# ATLAS.net
KiCad netlist of a schematic drawn in EasyEDA Pro
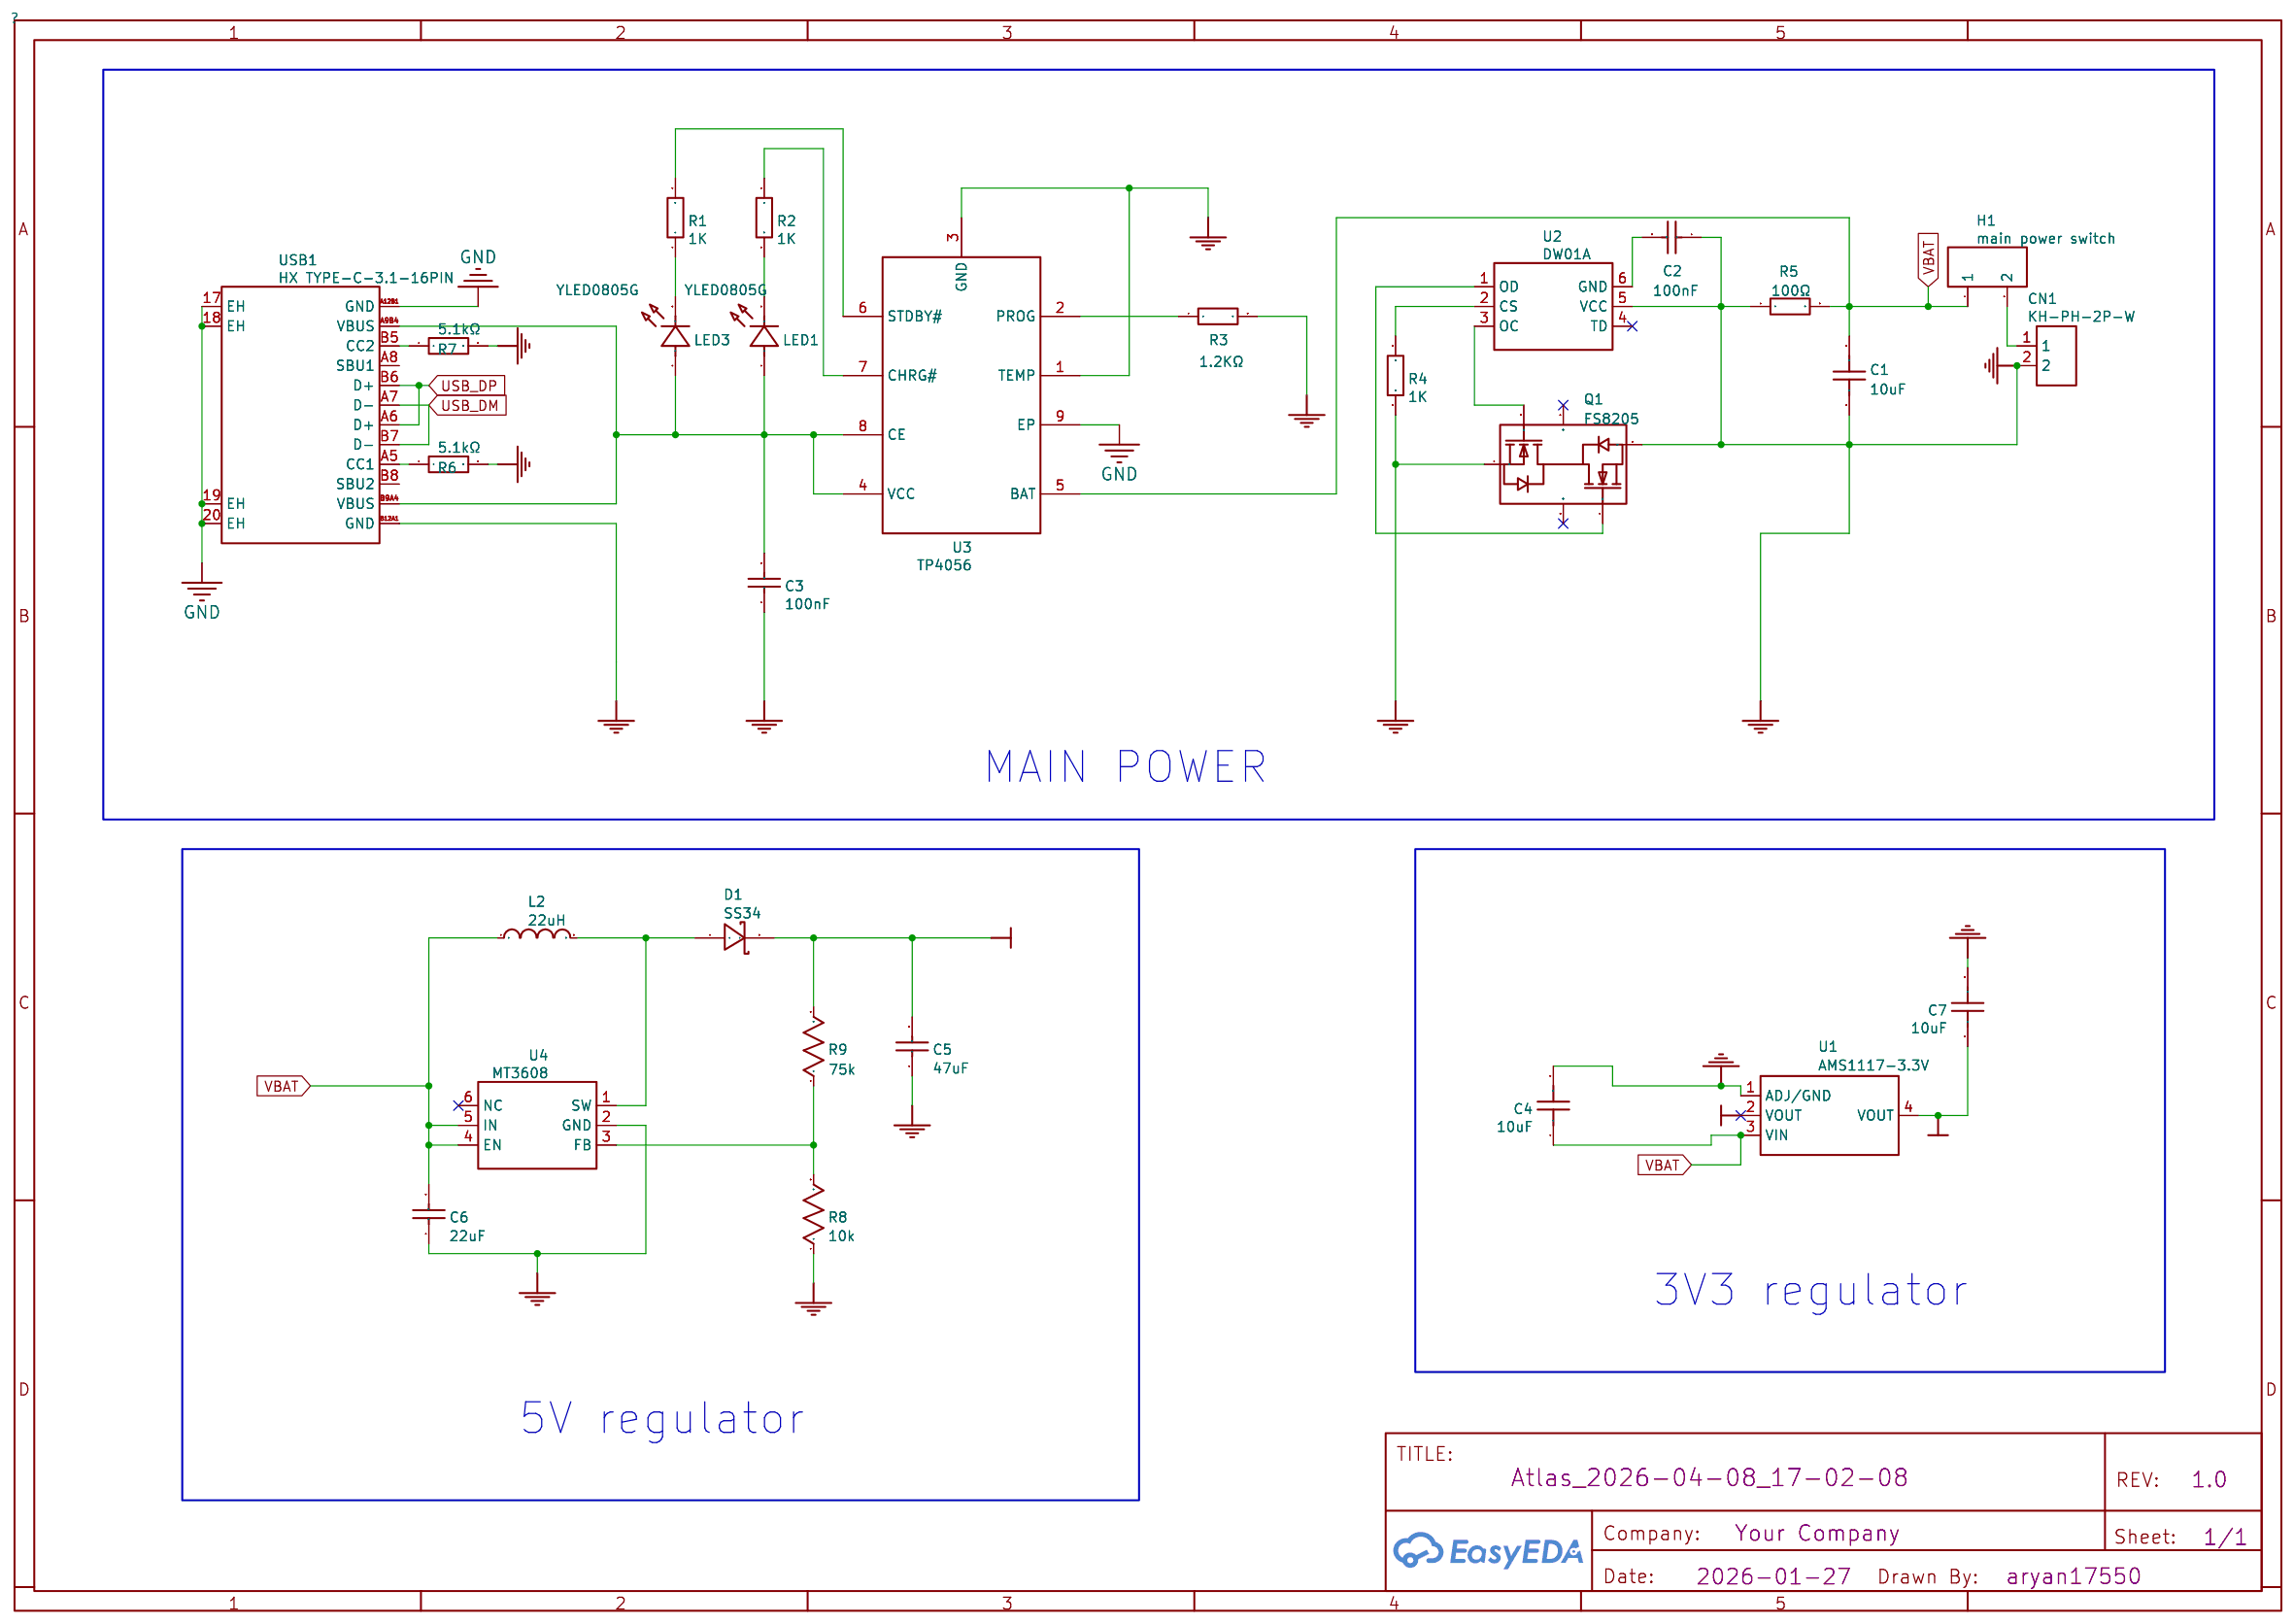
[diagram p0: Sheet_1]
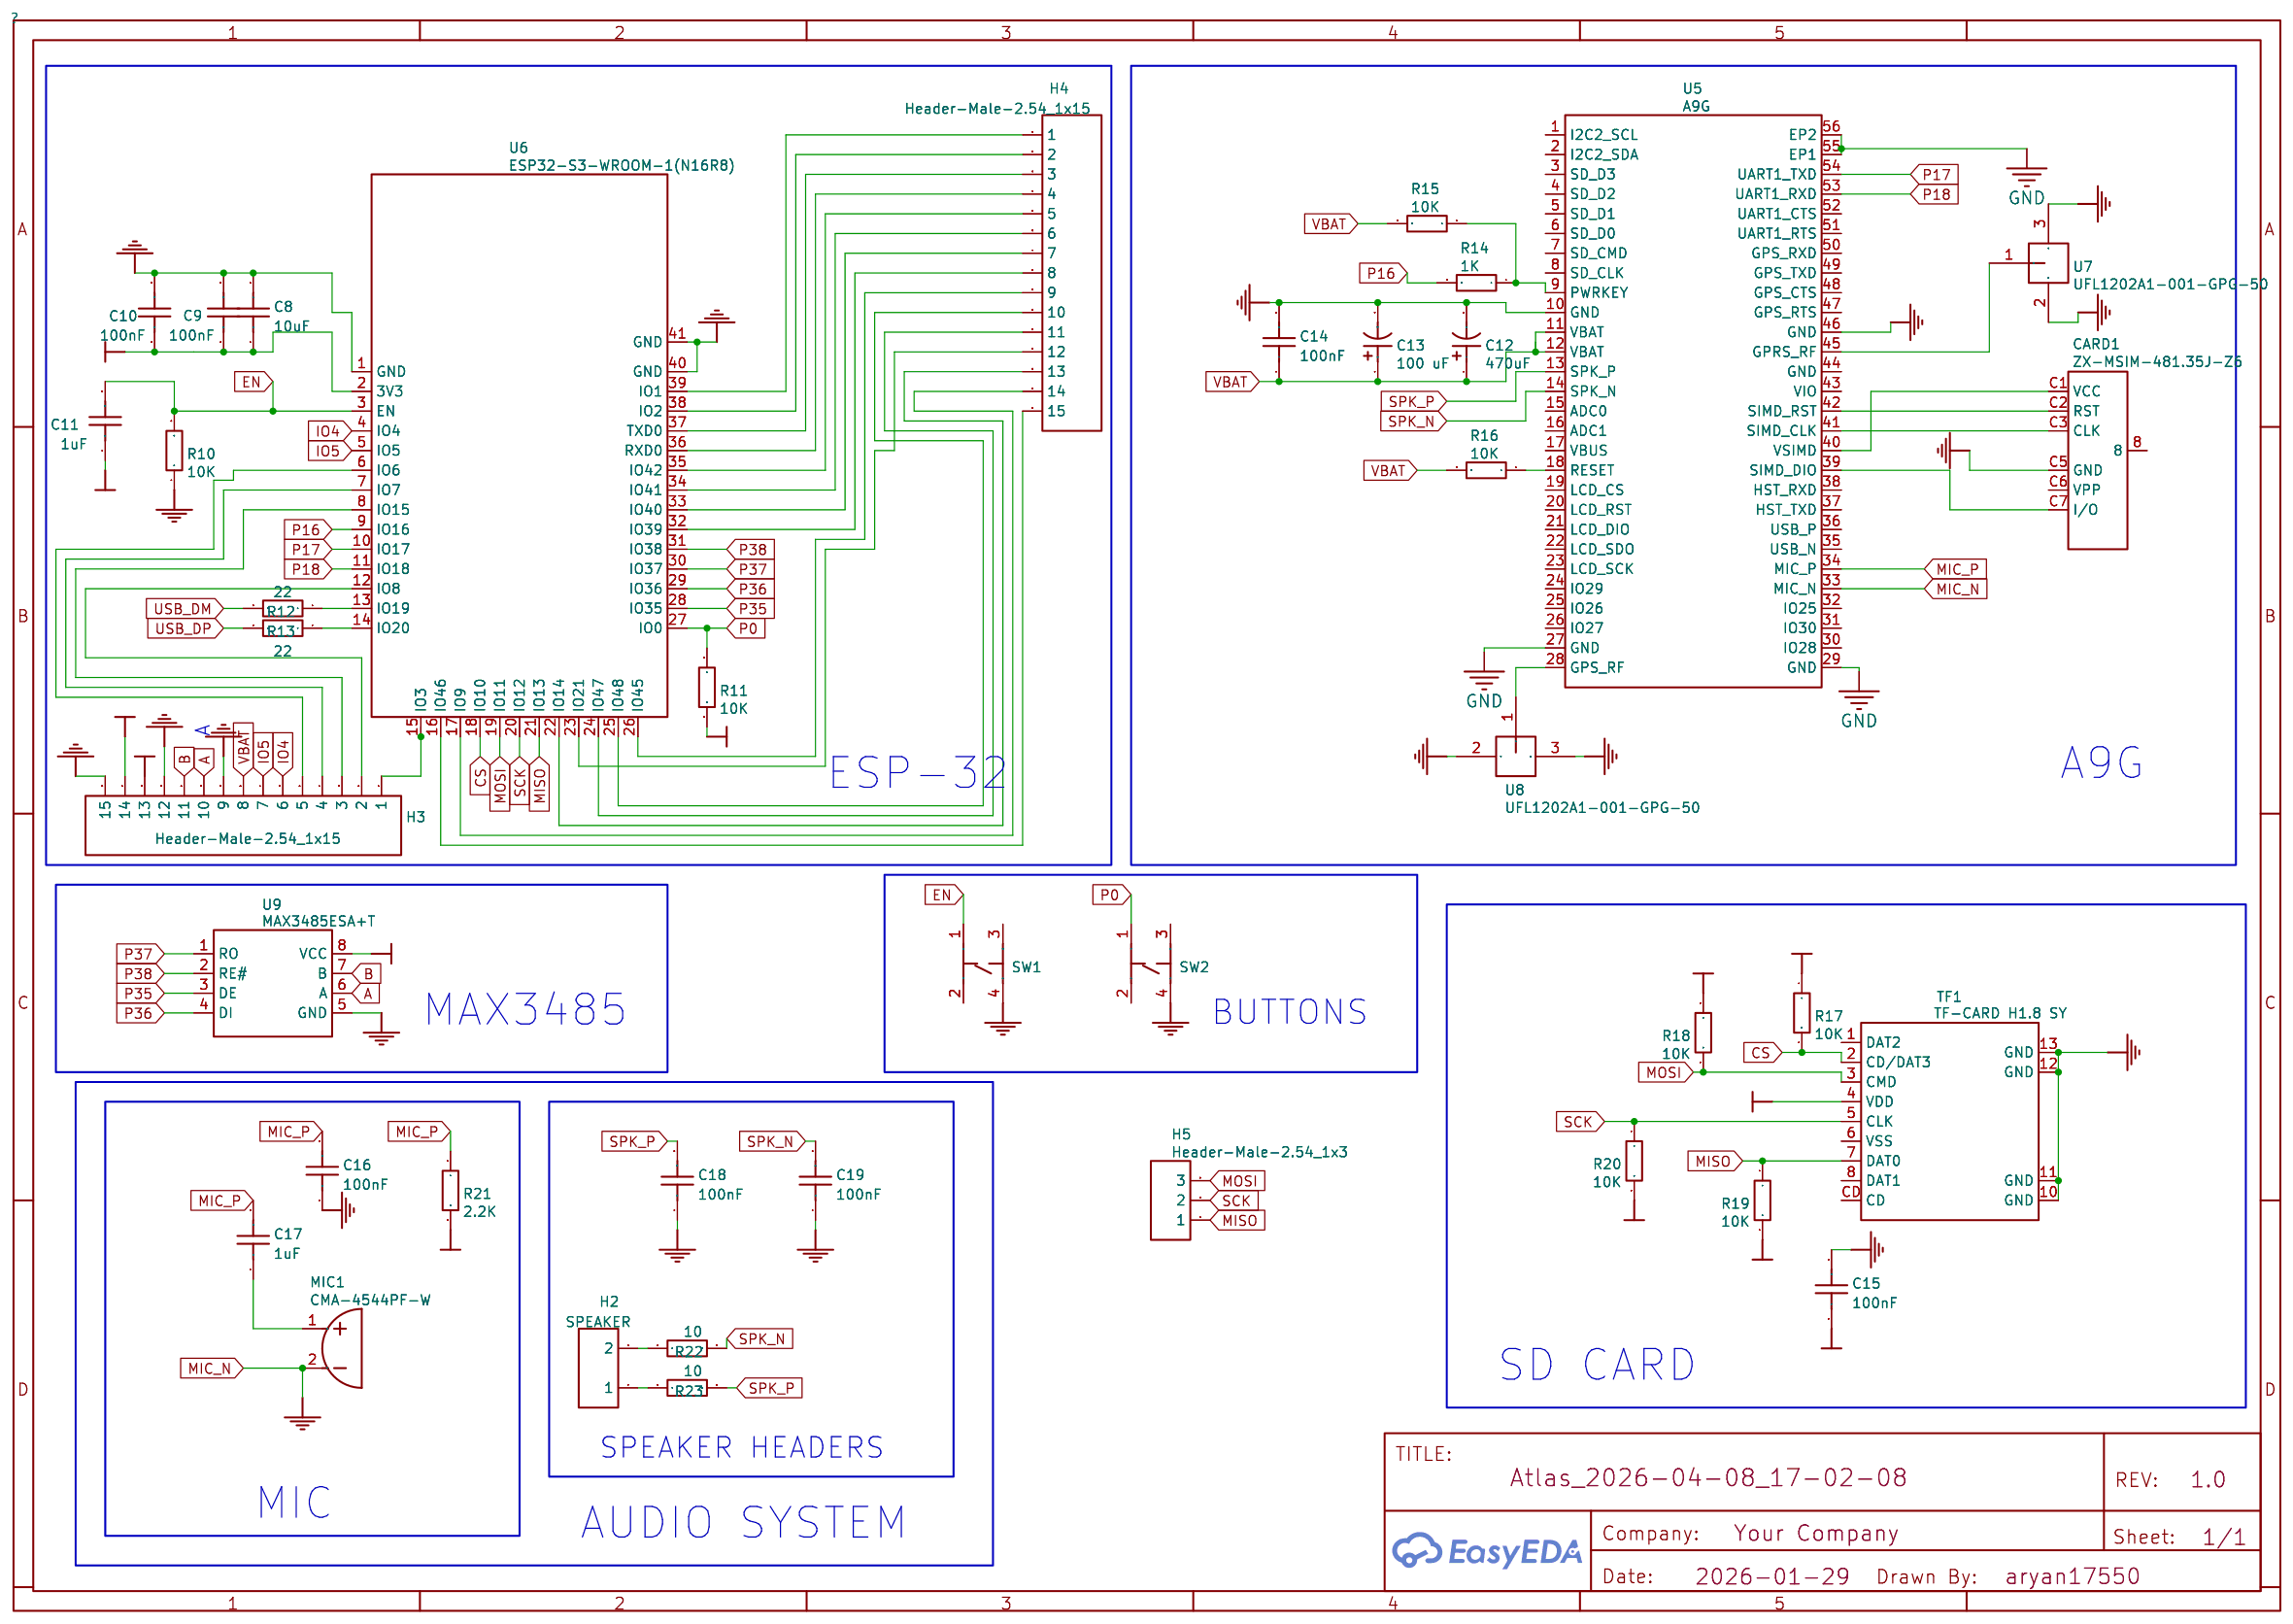
[diagram p1: Sheet_2]

(export (version "E")
  (design (tool "Eeschema 10.0.6"))
  (components
    (comp (ref "C1")
      (value "10uF")
      (footprint "easyedapro:C0603")
      (fields (field (name "Manufacturer Part") "CL10A106MP8NNNC") (field (name "Manufacturer") "SAMSUNG"))
      (libsource (lib "") (part "10uF_1"))
    )
    (comp (ref "C2")
      (value "100nF")
      (footprint "easyedapro:C0603")
      (fields (field (name "Manufacturer Part") "0603B104K250") (field (name "Manufacturer") "WTC"))
      (libsource (lib "easyedapro") (part "100nF"))
    )
    (comp (ref "C3")
      (value "100nF")
      (footprint "easyedapro:C0603")
      (fields (field (name "Manufacturer Part") "0603B104K250") (field (name "Manufacturer") "WTC"))
      (libsource (lib "easyedapro") (part "100nF"))
    )
    (comp (ref "C4")
      (value "10uF")
      (footprint "easyedapro:C0603")
      (fields (field (name "Manufacturer Part") "CL10A106MP8NNNC") (field (name "Manufacturer") "SAMSUNG"))
      (libsource (lib "easyedapro") (part "10uF"))
    )
    (comp (ref "C5")
      (value "47uF")
      (footprint "easyedapro:C0603")
      (fields (field (name "Manufacturer Part") "1812X226K250NT") (field (name "Manufacturer") "FH"))
      (libsource (lib "easyedapro") (part "47uF"))
    )
    (comp (ref "C6")
      (value "22uF")
      (footprint "easyedapro:C0603")
      (fields (field (name "Manufacturer Part") "1812X226K250NT") (field (name "Manufacturer") "FH"))
      (libsource (lib "easyedapro") (part "22uF"))
    )
    (comp (ref "C7")
      (value "10uF")
      (footprint "easyedapro:C0603")
      (fields (field (name "Manufacturer Part") "CL10A106MP8NNNC") (field (name "Manufacturer") "SAMSUNG"))
      (libsource (lib "easyedapro") (part "10uF"))
    )
    (comp (ref "CN1")
      (value "KH-PH-2P-W")
      (footprint "easyedapro:CONN-TH_2P-P2.00_KINGHELM_KH-PH-2P-W")
      (fields (field (name "Manufacturer") "kinghelm(金航标)") (field (name "Contributor") "LCSC"))
      (libsource (lib "easyedapro") (part "KH-PH-2P-W"))
    )
    (comp (ref "D1")
      (value "SS34")
      (footprint "easyedapro:SS34")
      (fields (field (name "Manufacturer") "MDD"))
      (libsource (lib "easyedapro") (part "SS34"))
    )
    (comp (ref "H1")
      (value "main power switch")
      (footprint "easyedapro:HDR-TH_2P-P2.54-V-M-1")
      (fields
        (field (name "Manufacturer Part") "826629-2")
        (field (name "Manufacturer") "TE Connectivity(泰科电子)")
      )
      (libsource (lib "easyedapro") (part "main power switch"))
    )
    (comp (ref "L2")
      (value "22uH")
      (footprint "easyedapro:IND-SMD_L12.5-W12.5_CYH125-22UH")
      (fields (field (name "Manufacturer Part") "SMRH74-220MT") (field (name "Manufacturer") "SXN(顺翔诺)"))
      (libsource (lib "easyedapro") (part "22uH"))
    )
    (comp (ref "LED1")
      (value "YLED0805G")
      (footprint "easyedapro:LED0805-FD-GREEN")
      (fields (field (name "Manufacturer") "YONGYUTAI(永裕泰)") (field (name "Contributor") "lcsc"))
      (libsource (lib "easyedapro") (part "YLED0805G"))
    )
    (comp (ref "LED3")
      (value "YLED0805G")
      (footprint "easyedapro:LED0805-FD-GREEN")
      (fields (field (name "Manufacturer") "YONGYUTAI(永裕泰)") (field (name "Contributor") "lcsc"))
      (libsource (lib "easyedapro") (part "YLED0805G"))
    )
    (comp (ref "Q1")
      (value "FS8205")
      (footprint "easyedapro:FS8205A")
      (fields (field (name "Manufacturer") "FORTUNE"))
      (libsource (lib "easyedapro") (part "FS8205"))
    )
    (comp (ref "R1")
      (value "1K")
      (footprint "easyedapro:R0603")
      (fields
        (field (name "Manufacturer Part") "ERJ3GEYJ102V")
        (field (name "Manufacturer") "PANASONIC")
        (field (name "Contributor") "LCSC")
      )
      (libsource (lib "easyedapro") (part "1K"))
    )
    (comp (ref "R2")
      (value "1K")
      (footprint "easyedapro:R0603")
      (fields
        (field (name "Manufacturer Part") "ERJ3GEYJ102V")
        (field (name "Manufacturer") "PANASONIC")
        (field (name "Contributor") "LCSC")
      )
      (libsource (lib "") (part "1K_1"))
    )
    (comp (ref "R3")
      (value "1.2KΩ")
      (footprint "easyedapro:R0603")
      (fields (field (name "Manufacturer Part") "RC0603JR-071K2L") (field (name "Manufacturer") "YAGEO"))
      (libsource (lib "easyedapro") (part "1.2KΩ"))
    )
    (comp (ref "R4")
      (value "1K")
      (footprint "easyedapro:R0603")
      (fields
        (field (name "Manufacturer Part") "ERJ3GEYJ102V")
        (field (name "Manufacturer") "PANASONIC")
        (field (name "Contributor") "LCSC")
      )
      (libsource (lib "easyedapro") (part "1K"))
    )
    (comp (ref "R5")
      (value "100Ω")
      (footprint "easyedapro:R0603")
      (fields (field (name "Manufacturer Part") "0603WAJ0101T5E") (field (name "Manufacturer") "UniOhm"))
      (libsource (lib "easyedapro") (part "100Ω"))
    )
    (comp (ref "R6")
      (value "5.1kΩ")
      (footprint "easyedapro:R0603")
      (fields
        (field (name "Manufacturer Part") "RMC06035.1K1%N")
        (field (name "Manufacturer") "Tyohm(幸亚电阻)")
        (field (name "Contributor") "LCSC")
      )
      (libsource (lib "easyedapro") (part "5.1kΩ"))
    )
    (comp (ref "R7")
      (value "5.1kΩ")
      (footprint "easyedapro:R0603")
      (fields
        (field (name "Manufacturer Part") "RMC06035.1K1%N")
        (field (name "Manufacturer") "Tyohm(幸亚电阻)")
        (field (name "Contributor") "LCSC")
      )
      (libsource (lib "easyedapro") (part "5.1kΩ"))
    )
    (comp (ref "R8")
      (value "10k")
      (footprint "easyedapro:R0603")
      (fields (field (name "Manufacturer Part") "?") (field (name "Manufacturer") "PANASONIC"))
      (libsource (lib "easyedapro") (part "10k"))
    )
    (comp (ref "R9")
      (value "75k")
      (footprint "easyedapro:R0603")
      (fields (field (name "Manufacturer Part") "?"))
      (libsource (lib "easyedapro") (part "75k"))
    )
    (comp (ref "U1")
      (value "AMS1117-3.3V")
      (footprint "easyedapro:SOT-223-4_L6.5-W3.5-P2.30-LS7.0-BR")
      (fields (field (name "Manufacturer") "WPMtek(维攀)") (field (name "Contributor") "LCSC"))
      (libsource (lib "easyedapro") (part "AMS1117-3.3V"))
    )
    (comp (ref "U2")
      (value "DW01A")
      (footprint "easyedapro:DW01A")
      (fields (field (name "Manufacturer") "PUOLOP") (field (name "Contributor") "LCSC"))
      (libsource (lib "easyedapro") (part "DW01A"))
    )
    (comp (ref "U3")
      (value "TP4056")
      (footprint "easyedapro:ESOP-8_L4.9-W3.9-P1.27-LS6.0-BL-EP")
      (fields
        (field (name "Manufacturer Part") "TP4056-42-ESOP8")
        (field (name "Manufacturer") "TOPPOWER(南京拓微)")
        (field (name "Contributor") "Guest")
      )
      (libsource (lib "easyedapro") (part "TP4056"))
    )
    (comp (ref "U4")
      (value "MT3608")
      (footprint "easyedapro:MT3608")
      (fields (field (name "Manufacturer") "AEROSEMI"))
      (libsource (lib "easyedapro") (part "MT3608"))
    )
    (comp (ref "USB1")
      (value "HX TYPE-C-3.1-16PIN")
      (footprint "easyedapro:TYPE-C-SMD_HX-TYPE-C-16PIN")
      (fields (field (name "Manufacturer") "hanxia(韩下)") (field (name "Contributor") "lcsc"))
      (libsource (lib "easyedapro") (part "HX TYPE-C-3.1-16PIN"))
    )
    (comp (ref "C8")
      (value "10uF")
      (footprint "easyedapro:C0603")
      (fields (field (name "Manufacturer Part") "CL10A106MP8NNNC") (field (name "Manufacturer") "SAMSUNG"))
      (libsource (lib "easyedapro") (part "10uF"))
    )
    (comp (ref "C9")
      (value "100nF")
      (footprint "easyedapro:C0603")
      (fields (field (name "Manufacturer Part") "CL10A106MP8NNNC") (field (name "Manufacturer") "SAMSUNG"))
      (libsource (lib "easyedapro") (part "100nF"))
    )
    (comp (ref "C10")
      (value "100nF")
      (footprint "easyedapro:C0603")
      (fields (field (name "Manufacturer Part") "CL10A106MP8NNNC") (field (name "Manufacturer") "SAMSUNG"))
      (libsource (lib "easyedapro") (part "100nF"))
    )
    (comp (ref "C11")
      (value "1uF")
      (footprint "easyedapro:C0603")
      (fields (field (name "Manufacturer Part") "CL10A106MP8NNNC") (field (name "Manufacturer") "SAMSUNG"))
      (libsource (lib "easyedapro") (part "1uF"))
    )
    (comp (ref "C12")
      (value "470uF")
      (footprint "easyedapro:CAP-SMD_BD10.0-L10.3-W10.3-LS11.3-FD")
      (fields
        (field (name "Manufacturer Part") "CS470UF35V167RV0136")
        (field (name "Manufacturer") "KNSCHA(科尼盛)")
        (field (name "Contributor") "lcsc")
      )
      (libsource (lib "easyedapro") (part "470uF"))
    )
    (comp (ref "C13")
      (value "100 uF")
      (footprint "easyedapro:CAP-SMD_BD10.0-L10.3-W10.3-LS11.3-FD")
      (fields
        (field (name "Manufacturer Part") "CS470UF35V167RV0136")
        (field (name "Manufacturer") "KNSCHA(科尼盛)")
        (field (name "Contributor") "lcsc")
      )
      (libsource (lib "easyedapro") (part "100 uF"))
    )
    (comp (ref "C14")
      (value "100nF")
      (footprint "easyedapro:C0603")
      (fields (field (name "Manufacturer Part") "CL10A106MP8NNNC") (field (name "Manufacturer") "SAMSUNG"))
      (libsource (lib "easyedapro") (part "100nF"))
    )
    (comp (ref "C15")
      (value "100nF")
      (footprint "easyedapro:C0603")
      (fields (field (name "Manufacturer Part") "CL10A106MP8NNNC") (field (name "Manufacturer") "SAMSUNG"))
      (libsource (lib "easyedapro") (part "100nF"))
    )
    (comp (ref "C16")
      (value "100nF")
      (footprint "easyedapro:C0603")
      (fields (field (name "Manufacturer Part") "CL10A106MP8NNNC") (field (name "Manufacturer") "SAMSUNG"))
      (libsource (lib "easyedapro") (part "100nF"))
    )
    (comp (ref "C17")
      (value "1uF")
      (footprint "easyedapro:C0603")
      (fields (field (name "Manufacturer Part") "CL10A106MP8NNNC") (field (name "Manufacturer") "SAMSUNG"))
      (libsource (lib "easyedapro") (part "1uF"))
    )
    (comp (ref "C18")
      (value "100nF")
      (footprint "easyedapro:C0603")
      (fields (field (name "Manufacturer Part") "CL10A106MP8NNNC") (field (name "Manufacturer") "SAMSUNG"))
      (libsource (lib "easyedapro") (part "100nF"))
    )
    (comp (ref "C19")
      (value "100nF")
      (footprint "easyedapro:C0603")
      (fields (field (name "Manufacturer Part") "CL10A106MP8NNNC") (field (name "Manufacturer") "SAMSUNG"))
      (libsource (lib "easyedapro") (part "100nF"))
    )
    (comp (ref "CARD1")
      (value "ZX-MSIM-481.35J-Z6")
      (footprint "easyedapro:SIM-SMD_ZX-MSIM-481.35J-Z6")
      (fields (field (name "Manufacturer") "Megastar(兆星)") (field (name "Contributor") "lcsc"))
      (libsource (lib "easyedapro") (part "ZX-MSIM-481.35J-Z6"))
    )
    (comp (ref "H2")
      (value "SPEAKER")
      (footprint "easyedapro:HDR-TH_2P-P2.54-V-M-1")
      (fields
        (field (name "Manufacturer Part") "826629-2")
        (field (name "Manufacturer") "TE Connectivity(泰科电子)")
      )
      (libsource (lib "easyedapro") (part "SPEAKER"))
    )
    (comp (ref "H3")
      (value "Header-Male-2.54_1x15")
      (footprint "easyedapro:HDR-TH_15P-P2.54-V-M")
      (fields
        (field (name "Manufacturer Part") "B-2100S15P-A110")
        (field (name "Manufacturer") "Ckmtw(灿科盟)")
        (field (name "Contributor") "LCSC")
      )
      (libsource (lib "easyedapro") (part "Header-Male-2.54_1x15"))
    )
    (comp (ref "H4")
      (value "Header-Male-2.54_1x15")
      (footprint "easyedapro:HDR-TH_15P-P2.54-V-M")
      (fields
        (field (name "Manufacturer Part") "B-2100S15P-A110")
        (field (name "Manufacturer") "Ckmtw(灿科盟)")
        (field (name "Contributor") "LCSC")
      )
      (libsource (lib "") (part "Header-Male-2.54_1x15_1"))
    )
    (comp (ref "H5")
      (value "Header-Male-2.54_1x3")
      (footprint "easyedapro:HDR-TH_3P-P2.54-V-M-1")
      (fields (field (name "Manufacturer Part") "2.54-1*3P针") (field (name "Manufacturer") "BOOMELE(博穆精密)"))
      (libsource (lib "easyedapro") (part "Header-Male-2.54_1x3"))
    )
    (comp (ref "MIC1")
      (value "CMA-4544PF-W")
      (footprint "easyedapro:MIC-TH_BD9.7-P2.50-D0.8-L-FD")
      (fields (field (name "Manufacturer") "CUI") (field (name "Contributor") "lcsc"))
      (libsource (lib "easyedapro") (part "CMA-4544PF-W"))
    )
    (comp (ref "R10")
      (value "10K")
      (footprint "easyedapro:R0603")
      (fields
        (field (name "Manufacturer Part") "ERJ3GEYJ102V")
        (field (name "Manufacturer") "PANASONIC")
        (field (name "Contributor") "LCSC")
      )
      (libsource (lib "") (part "10K_1"))
    )
    (comp (ref "R11")
      (value "10K")
      (footprint "easyedapro:R0603")
      (fields
        (field (name "Manufacturer Part") "ERJ3GEYJ102V")
        (field (name "Manufacturer") "PANASONIC")
        (field (name "Contributor") "LCSC")
      )
      (libsource (lib "") (part "10K_1"))
    )
    (comp (ref "R12")
      (value "22")
      (footprint "easyedapro:R0603")
      (fields
        (field (name "Manufacturer Part") "ERJ3GEYJ102V")
        (field (name "Manufacturer") "PANASONIC")
        (field (name "Contributor") "LCSC")
      )
      (libsource (lib "easyedapro") (part "22"))
    )
    (comp (ref "R13")
      (value "22")
      (footprint "easyedapro:R0603")
      (fields
        (field (name "Manufacturer Part") "ERJ3GEYJ102V")
        (field (name "Manufacturer") "PANASONIC")
        (field (name "Contributor") "LCSC")
      )
      (libsource (lib "easyedapro") (part "22"))
    )
    (comp (ref "R14")
      (value "1K")
      (footprint "easyedapro:R0603")
      (fields
        (field (name "Manufacturer Part") "ERJ3GEYJ102V")
        (field (name "Manufacturer") "PANASONIC")
        (field (name "Contributor") "LCSC")
      )
      (libsource (lib "easyedapro") (part "1K"))
    )
    (comp (ref "R15")
      (value "10K")
      (footprint "easyedapro:R0603")
      (fields
        (field (name "Manufacturer Part") "ERJ3GEYJ102V")
        (field (name "Manufacturer") "PANASONIC")
        (field (name "Contributor") "LCSC")
      )
      (libsource (lib "") (part "10K_2"))
    )
    (comp (ref "R16")
      (value "10K")
      (footprint "easyedapro:R0603")
      (fields
        (field (name "Manufacturer Part") "ERJ3GEYJ102V")
        (field (name "Manufacturer") "PANASONIC")
        (field (name "Contributor") "LCSC")
      )
      (libsource (lib "") (part "10K_2"))
    )
    (comp (ref "R17")
      (value "10K")
      (footprint "easyedapro:R0603")
      (fields
        (field (name "Manufacturer Part") "ERJ3GEYJ102V")
        (field (name "Manufacturer") "PANASONIC")
        (field (name "Contributor") "LCSC")
      )
      (libsource (lib "easyedapro") (part "10K"))
    )
    (comp (ref "R18")
      (value "10K")
      (footprint "easyedapro:R0603")
      (fields
        (field (name "Manufacturer Part") "ERJ3GEYJ102V")
        (field (name "Manufacturer") "PANASONIC")
        (field (name "Contributor") "LCSC")
      )
      (libsource (lib "easyedapro") (part "10K"))
    )
    (comp (ref "R19")
      (value "10K")
      (footprint "easyedapro:R0603")
      (fields
        (field (name "Manufacturer Part") "ERJ3GEYJ102V")
        (field (name "Manufacturer") "PANASONIC")
        (field (name "Contributor") "LCSC")
      )
      (libsource (lib "easyedapro") (part "10K"))
    )
    (comp (ref "R20")
      (value "10K")
      (footprint "easyedapro:R0603")
      (fields
        (field (name "Manufacturer Part") "ERJ3GEYJ102V")
        (field (name "Manufacturer") "PANASONIC")
        (field (name "Contributor") "LCSC")
      )
      (libsource (lib "easyedapro") (part "10K"))
    )
    (comp (ref "R21")
      (value "2.2K")
      (footprint "easyedapro:R0603")
      (fields
        (field (name "Manufacturer Part") "ERJ3GEYJ102V")
        (field (name "Manufacturer") "PANASONIC")
        (field (name "Contributor") "LCSC")
      )
      (libsource (lib "easyedapro") (part "2.2K"))
    )
    (comp (ref "R22")
      (value "10")
      (footprint "easyedapro:R0603")
      (fields
        (field (name "Manufacturer Part") "ERJ3GEYJ102V")
        (field (name "Manufacturer") "PANASONIC")
        (field (name "Contributor") "LCSC")
      )
      (libsource (lib "easyedapro") (part "10"))
    )
    (comp (ref "R23")
      (value "10")
      (footprint "easyedapro:R0603")
      (fields
        (field (name "Manufacturer Part") "ERJ3GEYJ102V")
        (field (name "Manufacturer") "PANASONIC")
        (field (name "Contributor") "LCSC")
      )
      (libsource (lib "easyedapro") (part "10"))
    )
    (comp (ref "SW1")
      (value "HX-6X6X7.3-TP FT SQUARE BUTTON")
      (footprint "easyedapro:SW-SMD_4P-L6.0-W6.0-P4.50-LS9.0-H7.3")
      (fields
        (field (name "Manufacturer Part") "HX-6x6x7.3-TP FT square button")
        (field (name "Manufacturer") "hanxia(韩下)")
        (field (name "Contributor") "lcsc")
      )
      (libsource (lib "easyedapro") (part "HX-6X6X7.3-TP FT SQUARE BUTTON"))
    )
    (comp (ref "SW2")
      (value "HX-6X6X7.3-TP FT SQUARE BUTTON")
      (footprint "easyedapro:SW-SMD_4P-L6.0-W6.0-P4.50-LS9.0-H7.3")
      (fields
        (field (name "Manufacturer Part") "HX-6x6x7.3-TP FT square button")
        (field (name "Manufacturer") "hanxia(韩下)")
        (field (name "Contributor") "lcsc")
      )
      (libsource (lib "easyedapro") (part "HX-6X6X7.3-TP FT SQUARE BUTTON"))
    )
    (comp (ref "TF1")
      (value "TF-CARD H1.8 SY")
      (footprint "easyedapro:TF-SMD_TF-012")
      (fields (field (name "Manufacturer") "SHOU HAN(首韩)") (field (name "Contributor") "lcsc"))
      (libsource (lib "easyedapro") (part "TF-CARD H1.8 SY"))
    )
    (comp (ref "U5")
      (value "A9G")
      (footprint "easyedapro:GSM-SMD_A9-GSM-GPRSMODULE")
      (fields (field (name "Manufacturer") "Ai-Thinker(安信可)") (field (name "Contributor") "lcsc"))
      (libsource (lib "easyedapro") (part "A9G"))
    )
    (comp (ref "U6")
      (value "ESP32-S3-WROOM-1(N16R8)")
      (footprint "easyedapro:WIRELM-SMD_ESP32-S3-WROOM-1")
      (fields
        (field (name "Manufacturer Part") "ESP32-S3-WROOM-1-N16R8")
        (field (name "Manufacturer") "ESPRESSIF(乐鑫)")
        (field (name "Contributor") "lcsc")
      )
      (libsource (lib "easyedapro") (part "ESP32-S3-WROOM-1(N16R8)"))
    )
    (comp (ref "U7")
      (value "UFL1202A1-001-GPG-50")
      (footprint "easyedapro:IPEX-SMD_UFL1202A1-001-GPG-50")
      (fields (field (name "Contributor") "lcsc"))
      (libsource (lib "easyedapro") (part "UFL1202A1-001-GPG-50"))
    )
    (comp (ref "U8")
      (value "UFL1202A1-001-GPG-50")
      (footprint "easyedapro:IPEX-SMD_UFL1202A1-001-GPG-50")
      (fields (field (name "Contributor") "lcsc"))
      (libsource (lib "") (part "UFL1202A1-001-GPG-50_1"))
    )
    (comp (ref "U9")
      (value "MAX3485ESA+T")
      (footprint "easyedapro:SOIC-8_L4.9-W3.9-P1.27-LS6.0-BL")
      (fields (field (name "Manufacturer") "ADI(亚德诺)/MAXIM(美信)"))
      (libsource (lib "easyedapro") (part "MAX3485ESA+T"))
    )
  )
  (nets
    (net (code "1") (name "+3V3") (class "Default")
      (node (ref "C10") (pin "1") (pinfunction "1_1") (pintype "unspecified"))
      (node (ref "C11") (pin "1") (pinfunction "1_1") (pintype "unspecified"))
      (node (ref "C15") (pin "1") (pinfunction "1_1") (pintype "unspecified"))
      (node (ref "C7") (pin "1") (pinfunction "1_1") (pintype "unspecified"))
      (node (ref "C8") (pin "1") (pinfunction "1_1") (pintype "unspecified"))
      (node (ref "C9") (pin "1") (pinfunction "1_1") (pintype "unspecified"))
      (node (ref "H3") (pin "14") (pinfunction "14_14") (pintype "unspecified"))
      (node (ref "R11") (pin "1") (pinfunction "1_1") (pintype "unspecified"))
      (node (ref "R17") (pin "1") (pinfunction "1_1") (pintype "unspecified"))
      (node (ref "R18") (pin "1") (pinfunction "1_1") (pintype "unspecified"))
      (node (ref "R19") (pin "2") (pinfunction "2_2") (pintype "unspecified"))
      (node (ref "R20") (pin "2") (pinfunction "2_2") (pintype "unspecified"))
      (node (ref "R21") (pin "2") (pinfunction "2_2") (pintype "unspecified"))
      (node (ref "TF1") (pin "4") (pinfunction "VDD_4") (pintype "unspecified"))
      (node (ref "U1") (pin "2") (pinfunction "VOUT_2") (pintype "unspecified"))
      (node (ref "U1") (pin "4") (pinfunction "VOUT_4") (pintype "unspecified"))
      (node (ref "U6") (pin "2") (pinfunction "3V3_2") (pintype "unspecified"))
      (node (ref "U9") (pin "8") (pinfunction "VCC_8") (pintype "unspecified"))
    )
    (net (code "2") (name "+5V") (class "Default")
      (node (ref "C5") (pin "2") (pinfunction "2_2") (pintype "input"))
      (node (ref "D1") (pin "2") (pinfunction "K_2") (pintype "unspecified"))
      (node (ref "H3") (pin "13") (pinfunction "13_13") (pintype "unspecified"))
      (node (ref "R9") (pin "2") (pinfunction "2_2") (pintype "unspecified"))
    )
    (net (code "3") (name "A") (class "Default")
      (node (ref "H3") (pin "10") (pinfunction "10_10") (pintype "unspecified"))
      (node (ref "U9") (pin "6") (pinfunction "A_6") (pintype "unspecified"))
    )
    (net (code "4") (name "B") (class "Default")
      (node (ref "H3") (pin "11") (pinfunction "11_11") (pintype "unspecified"))
      (node (ref "U9") (pin "7") (pinfunction "B_7") (pintype "unspecified"))
    )
    (net (code "5") (name "CS") (class "Default")
      (node (ref "R17") (pin "2") (pinfunction "2_2") (pintype "unspecified"))
      (node (ref "TF1") (pin "2") (pinfunction "CD/DAT3_2") (pintype "unspecified"))
      (node (ref "U6") (pin "18") (pinfunction "IO10_18") (pintype "unspecified"))
    )
    (net (code "6") (name "EN") (class "Default")
      (node (ref "C11") (pin "2") (pinfunction "2_2") (pintype "unspecified"))
      (node (ref "R10") (pin "2") (pinfunction "2_2") (pintype "unspecified"))
      (node (ref "SW1") (pin "1") (pinfunction "A_1") (pintype "unspecified"))
      (node (ref "U6") (pin "3") (pinfunction "EN_3") (pintype "unspecified"))
    )
    (net (code "7") (name "IO4") (class "Default")
      (node (ref "H3") (pin "6") (pinfunction "6_6") (pintype "unspecified"))
      (node (ref "U6") (pin "4") (pinfunction "IO4_4") (pintype "unspecified"))
    )
    (net (code "8") (name "IO5") (class "Default")
      (node (ref "H3") (pin "7") (pinfunction "7_7") (pintype "unspecified"))
      (node (ref "U6") (pin "5") (pinfunction "IO5_5") (pintype "unspecified"))
    )
    (net (code "9") (name "MIC_N") (class "Default")
      (node (ref "C1") (pin "1") (pinfunction "1_1") (pintype "unspecified"))
      (node (ref "C10") (pin "2") (pinfunction "2_2") (pintype "unspecified"))
      (node (ref "C12") (pin "2") (pinfunction "2_2") (pintype "input"))
      (node (ref "C13") (pin "2") (pinfunction "2_2") (pintype "input"))
      (node (ref "C14") (pin "2") (pinfunction "2_2") (pintype "unspecified"))
      (node (ref "C15") (pin "2") (pinfunction "2_2") (pintype "unspecified"))
      (node (ref "C16") (pin "1") (pinfunction "1_1") (pintype "unspecified"))
      (node (ref "C18") (pin "1") (pinfunction "1_1") (pintype "unspecified"))
      (node (ref "C19") (pin "1") (pinfunction "1_1") (pintype "unspecified"))
      (node (ref "C2") (pin "1") (pinfunction "1_1") (pintype "input"))
      (node (ref "C3") (pin "1") (pinfunction "1_1") (pintype "input"))
      (node (ref "C4") (pin "2") (pinfunction "2_2") (pintype "unspecified"))
      (node (ref "C5") (pin "1") (pinfunction "1_1") (pintype "input"))
      (node (ref "C6") (pin "1") (pinfunction "1_1") (pintype "input"))
      (node (ref "C7") (pin "2") (pinfunction "2_2") (pintype "unspecified"))
      (node (ref "C8") (pin "2") (pinfunction "2_2") (pintype "unspecified"))
      (node (ref "C9") (pin "2") (pinfunction "2_2") (pintype "unspecified"))
      (node (ref "CARD1") (pin "C5") (pinfunction "GND_C5") (pintype "unspecified"))
      (node (ref "CN1") (pin "2") (pinfunction "2_2") (pintype "unspecified"))
      (node (ref "H3") (pin "12") (pinfunction "12_12") (pintype "unspecified"))
      (node (ref "H3") (pin "15") (pinfunction "15_15") (pintype "unspecified"))
      (node (ref "H3") (pin "9") (pinfunction "9_9") (pintype "unspecified"))
      (node (ref "MIC1") (pin "2") (pinfunction "2_2") (pintype "unspecified"))
      (node (ref "Q1") (pin "1") (pinfunction "S1_1") (pintype "unspecified"))
      (node (ref "Q1") (pin "3") (pinfunction "S2_3") (pintype "unspecified"))
      (node (ref "R10") (pin "1") (pinfunction "1_1") (pintype "unspecified"))
      (node (ref "R3") (pin "2") (pinfunction "2_2") (pintype "input"))
      (node (ref "R4") (pin "1") (pinfunction "1_1") (pintype "unspecified"))
      (node (ref "R5") (pin "1") (pinfunction "1_1") (pintype "input"))
      (node (ref "R6") (pin "2") (pinfunction "2_2") (pintype "unspecified"))
      (node (ref "R7") (pin "2") (pinfunction "2_2") (pintype "unspecified"))
      (node (ref "R8") (pin "1") (pinfunction "1_1") (pintype "unspecified"))
      (node (ref "SW1") (pin "4") (pinfunction "D_4") (pintype "unspecified"))
      (node (ref "SW2") (pin "4") (pinfunction "D_4") (pintype "unspecified"))
      (node (ref "TF1") (pin "10") (pinfunction "GND_10") (pintype "unspecified"))
      (node (ref "TF1") (pin "11") (pinfunction "GND_11") (pintype "unspecified"))
      (node (ref "TF1") (pin "12") (pinfunction "GND_12") (pintype "unspecified"))
      (node (ref "TF1") (pin "13") (pinfunction "GND_13") (pintype "unspecified"))
      (node (ref "U1") (pin "1") (pinfunction "ADJ/GND_1") (pintype "unspecified"))
      (node (ref "U2") (pin "5") (pinfunction "VCC_5") (pintype "unspecified"))
      (node (ref "U3") (pin "1") (pinfunction "TEMP_1") (pintype "unspecified"))
      (node (ref "U3") (pin "3") (pinfunction "GND_3") (pintype "unspecified"))
      (node (ref "U3") (pin "9") (pinfunction "EP_9") (pintype "unspecified"))
      (node (ref "U4") (pin "2") (pinfunction "GND_2") (pintype "unspecified"))
      (node (ref "U5") (pin "10") (pinfunction "GND_10") (pintype "unspecified"))
      (node (ref "U5") (pin "27") (pinfunction "GND_27") (pintype "unspecified"))
      (node (ref "U5") (pin "29") (pinfunction "GND_29") (pintype "unspecified"))
      (node (ref "U5") (pin "33") (pinfunction "MIC_N_33") (pintype "unspecified"))
      (node (ref "U5") (pin "46") (pinfunction "GND_46") (pintype "unspecified"))
      (node (ref "U5") (pin "55") (pinfunction "EP1_55") (pintype "unspecified"))
      (node (ref "U5") (pin "56") (pinfunction "EP2_56") (pintype "unspecified"))
      (node (ref "U6") (pin "1") (pinfunction "GND_1") (pintype "unspecified"))
      (node (ref "U6") (pin "40") (pinfunction "GND_40") (pintype "unspecified"))
      (node (ref "U6") (pin "41") (pinfunction "GND_41") (pintype "unspecified"))
      (node (ref "U7") (pin "2") (pinfunction "2_2") (pintype "unspecified"))
      (node (ref "U7") (pin "3") (pinfunction "3_3") (pintype "unspecified"))
      (node (ref "U8") (pin "2") (pinfunction "2_2") (pintype "unspecified"))
      (node (ref "U8") (pin "3") (pinfunction "3_3") (pintype "unspecified"))
      (node (ref "U9") (pin "5") (pinfunction "GND_5") (pintype "unspecified"))
      (node (ref "USB1") (pin "17") (pinfunction "EH_17") (pintype "unspecified"))
      (node (ref "USB1") (pin "18") (pinfunction "EH_18") (pintype "unspecified"))
      (node (ref "USB1") (pin "19") (pinfunction "EH_19") (pintype "unspecified"))
      (node (ref "USB1") (pin "20") (pinfunction "EH_20") (pintype "unspecified"))
      (node (ref "USB1") (pin "A12B1") (pinfunction "GND_A12B1") (pintype "unspecified"))
      (node (ref "USB1") (pin "B12A1") (pinfunction "GND_B12A1") (pintype "unspecified"))
    )
    (net (code "10") (name "MIC_P") (class "Default")
      (node (ref "C16") (pin "2") (pinfunction "2_2") (pintype "unspecified"))
      (node (ref "C17") (pin "2") (pinfunction "2_2") (pintype "unspecified"))
      (node (ref "R21") (pin "1") (pinfunction "1_1") (pintype "unspecified"))
      (node (ref "U5") (pin "34") (pinfunction "MIC_P_34") (pintype "unspecified"))
    )
    (net (code "11") (name "MISO") (class "Default")
      (node (ref "H5") (pin "1") (pinfunction "1_1") (pintype "input"))
      (node (ref "R19") (pin "1") (pinfunction "1_1") (pintype "unspecified"))
      (node (ref "TF1") (pin "7") (pinfunction "DAT0_7") (pintype "unspecified"))
      (node (ref "U6") (pin "21") (pinfunction "IO13_21") (pintype "unspecified"))
    )
    (net (code "12") (name "MOSI") (class "Default")
      (node (ref "H5") (pin "3") (pinfunction "3_3") (pintype "input"))
      (node (ref "R18") (pin "2") (pinfunction "2_2") (pintype "unspecified"))
      (node (ref "TF1") (pin "3") (pinfunction "CMD_3") (pintype "unspecified"))
      (node (ref "U6") (pin "19") (pinfunction "IO11_19") (pintype "unspecified"))
    )
    (net (code "13") (name "Net-(C17-Pad1)") (class "Default")
      (node (ref "C17") (pin "1") (pinfunction "1_1") (pintype "unspecified"))
      (node (ref "MIC1") (pin "1") (pinfunction "1_1") (pintype "unspecified"))
    )
    (net (code "14") (name "Net-(CARD1-CLK)") (class "Default")
      (node (ref "CARD1") (pin "C3") (pinfunction "CLK_C3") (pintype "unspecified"))
      (node (ref "U5") (pin "41") (pinfunction "SIMD_CLK_41") (pintype "unspecified"))
    )
    (net (code "15") (name "Net-(CARD1-I{slash}O)") (class "Default")
      (node (ref "CARD1") (pin "C7") (pinfunction "I/O_C7") (pintype "unspecified"))
      (node (ref "U5") (pin "39") (pinfunction "SIMD_DIO_39") (pintype "unspecified"))
    )
    (net (code "16") (name "Net-(CARD1-RST)") (class "Default")
      (node (ref "CARD1") (pin "C2") (pinfunction "RST_C2") (pintype "unspecified"))
      (node (ref "U5") (pin "42") (pinfunction "SIMD_RST_42") (pintype "unspecified"))
    )
    (net (code "17") (name "Net-(CARD1-VCC)") (class "Default")
      (node (ref "CARD1") (pin "C1") (pinfunction "VCC_C1") (pintype "unspecified"))
      (node (ref "U5") (pin "40") (pinfunction "VSIMD_40") (pintype "unspecified"))
    )
    (net (code "18") (name "Net-(CN1-Pad1)") (class "Default")
      (node (ref "CN1") (pin "1") (pinfunction "1_1") (pintype "unspecified"))
      (node (ref "H1") (pin "2") (pinfunction "2_2") (pintype "unspecified"))
    )
    (net (code "19") (name "Net-(D1-A)") (class "Default")
      (node (ref "D1") (pin "1") (pinfunction "A_1") (pintype "unspecified"))
      (node (ref "L2") (pin "2") (pinfunction "2_2") (pintype "unspecified"))
      (node (ref "U4") (pin "1") (pinfunction "SW_1") (pintype "unspecified"))
    )
    (net (code "20") (name "Net-(H2-Pad1)") (class "Default")
      (node (ref "H2") (pin "1") (pinfunction "1_1") (pintype "unspecified"))
      (node (ref "R23") (pin "1") (pinfunction "1_1") (pintype "unspecified"))
    )
    (net (code "21") (name "Net-(H2-Pad2)") (class "Default")
      (node (ref "H2") (pin "2") (pinfunction "2_2") (pintype "unspecified"))
      (node (ref "R22") (pin "1") (pinfunction "1_1") (pintype "unspecified"))
    )
    (net (code "22") (name "Net-(LED1-A)") (class "Default")
      (node (ref "C3") (pin "2") (pinfunction "2_2") (pintype "input"))
      (node (ref "LED1") (pin "1") (pinfunction "A_1") (pintype "unspecified"))
      (node (ref "LED3") (pin "1") (pinfunction "A_1") (pintype "unspecified"))
      (node (ref "U3") (pin "4") (pinfunction "VCC_4") (pintype "unspecified"))
      (node (ref "U3") (pin "8") (pinfunction "CE_8") (pintype "unspecified"))
      (node (ref "USB1") (pin "A9B4") (pinfunction "VBUS_A9B4") (pintype "unspecified"))
      (node (ref "USB1") (pin "B9A4") (pinfunction "VBUS_B9A4") (pintype "unspecified"))
    )
    (net (code "23") (name "Net-(LED1-K)") (class "Default")
      (node (ref "LED1") (pin "2") (pinfunction "K_2") (pintype "unspecified"))
      (node (ref "R2") (pin "2") (pinfunction "2_2") (pintype "unspecified"))
    )
    (net (code "24") (name "Net-(LED3-K)") (class "Default")
      (node (ref "LED3") (pin "2") (pinfunction "K_2") (pintype "unspecified"))
      (node (ref "R1") (pin "1") (pinfunction "1_1") (pintype "unspecified"))
    )
    (net (code "25") (name "Net-(Q1-G1)") (class "Default")
      (node (ref "Q1") (pin "6") (pinfunction "G1_6") (pintype "unspecified"))
      (node (ref "U2") (pin "3") (pinfunction "OC_3") (pintype "unspecified"))
    )
    (net (code "26") (name "Net-(Q1-G2)") (class "Default")
      (node (ref "Q1") (pin "4") (pinfunction "G2_4") (pintype "unspecified"))
      (node (ref "U2") (pin "1") (pinfunction "OD_1") (pintype "unspecified"))
    )
    (net (code "27") (name "Net-(U2-CS)") (class "Default")
      (node (ref "R4") (pin "2") (pinfunction "2_2") (pintype "unspecified"))
      (node (ref "U2") (pin "2") (pinfunction "CS_2") (pintype "unspecified"))
    )
    (net (code "28") (name "Net-(U2-GND)") (class "Default")
      (node (ref "C2") (pin "2") (pinfunction "2_2") (pintype "input"))
      (node (ref "U2") (pin "6") (pinfunction "GND_6") (pintype "unspecified"))
    )
    (net (code "29") (name "Net-(U3-CHRG#)") (class "Default")
      (node (ref "R2") (pin "1") (pinfunction "1_1") (pintype "unspecified"))
      (node (ref "U3") (pin "7") (pinfunction "CHRG#_7") (pintype "unspecified"))
    )
    (net (code "30") (name "Net-(U3-PROG)") (class "Default")
      (node (ref "R3") (pin "1") (pinfunction "1_1") (pintype "input"))
      (node (ref "U3") (pin "2") (pinfunction "PROG_2") (pintype "unspecified"))
    )
    (net (code "31") (name "Net-(U3-STDBY#)") (class "Default")
      (node (ref "R1") (pin "2") (pinfunction "2_2") (pintype "unspecified"))
      (node (ref "U3") (pin "6") (pinfunction "STDBY#_6") (pintype "unspecified"))
    )
    (net (code "32") (name "Net-(U4-FB)") (class "Default")
      (node (ref "R8") (pin "2") (pinfunction "2_2") (pintype "unspecified"))
      (node (ref "R9") (pin "1") (pinfunction "1_1") (pintype "unspecified"))
      (node (ref "U4") (pin "3") (pinfunction "FB_3") (pintype "unspecified"))
    )
    (net (code "33") (name "Net-(U5-GPRS_RF)") (class "Default")
      (node (ref "U5") (pin "45") (pinfunction "GPRS_RF_45") (pintype "unspecified"))
      (node (ref "U7") (pin "1") (pinfunction "1_1") (pintype "unspecified"))
    )
    (net (code "34") (name "Net-(U5-GPS_RF)") (class "Default")
      (node (ref "U5") (pin "28") (pinfunction "GPS_RF_28") (pintype "unspecified"))
      (node (ref "U8") (pin "1") (pinfunction "1_1") (pintype "unspecified"))
    )
    (net (code "35") (name "Net-(U5-PWRKEY)") (class "Default")
      (node (ref "R14") (pin "1") (pinfunction "1_1") (pintype "unspecified"))
      (node (ref "R15") (pin "1") (pinfunction "1_1") (pintype "unspecified"))
      (node (ref "U5") (pin "9") (pinfunction "PWRKEY_9") (pintype "unspecified"))
    )
    (net (code "36") (name "Net-(U5-RESET)") (class "Default")
      (node (ref "R16") (pin "1") (pinfunction "1_1") (pintype "unspecified"))
      (node (ref "U5") (pin "18") (pinfunction "RESET_18") (pintype "unspecified"))
    )
    (net (code "37") (name "Net-(U6-IO1)") (class "Default")
      (node (ref "H4") (pin "1") (pinfunction "1_1") (pintype "unspecified"))
      (node (ref "U6") (pin "39") (pinfunction "IO1_39") (pintype "unspecified"))
    )
    (net (code "38") (name "Net-(U6-IO2)") (class "Default")
      (node (ref "H4") (pin "2") (pinfunction "2_2") (pintype "unspecified"))
      (node (ref "U6") (pin "38") (pinfunction "IO2_38") (pintype "unspecified"))
    )
    (net (code "39") (name "Net-(U6-IO3)") (class "Default")
      (node (ref "H3") (pin "1") (pinfunction "1_1") (pintype "unspecified"))
      (node (ref "U6") (pin "15") (pinfunction "IO3_15") (pintype "unspecified"))
    )
    (net (code "40") (name "Net-(U6-IO6)") (class "Default")
      (node (ref "H3") (pin "5") (pinfunction "5_5") (pintype "unspecified"))
      (node (ref "U6") (pin "6") (pinfunction "IO6_6") (pintype "unspecified"))
    )
    (net (code "41") (name "Net-(U6-IO7)") (class "Default")
      (node (ref "H3") (pin "4") (pinfunction "4_4") (pintype "unspecified"))
      (node (ref "U6") (pin "7") (pinfunction "IO7_7") (pintype "unspecified"))
    )
    (net (code "42") (name "Net-(U6-IO8)") (class "Default")
      (node (ref "H3") (pin "2") (pinfunction "2_2") (pintype "unspecified"))
      (node (ref "U6") (pin "12") (pinfunction "IO8_12") (pintype "unspecified"))
    )
    (net (code "43") (name "Net-(U6-IO9)") (class "Default")
      (node (ref "H4") (pin "14") (pinfunction "14_14") (pintype "unspecified"))
      (node (ref "U6") (pin "17") (pinfunction "IO9_17") (pintype "unspecified"))
    )
    (net (code "44") (name "Net-(U6-IO14)") (class "Default")
      (node (ref "H4") (pin "13") (pinfunction "13_13") (pintype "unspecified"))
      (node (ref "U6") (pin "22") (pinfunction "IO14_22") (pintype "unspecified"))
    )
    (net (code "45") (name "Net-(U6-IO15)") (class "Default")
      (node (ref "H3") (pin "3") (pinfunction "3_3") (pintype "unspecified"))
      (node (ref "U6") (pin "8") (pinfunction "IO15_8") (pintype "unspecified"))
    )
    (net (code "46") (name "Net-(U6-IO19)") (class "Default")
      (node (ref "R12") (pin "1") (pinfunction "1_1") (pintype "unspecified"))
      (node (ref "U6") (pin "13") (pinfunction "IO19_13") (pintype "unspecified"))
    )
    (net (code "47") (name "Net-(U6-IO20)") (class "Default")
      (node (ref "R13") (pin "1") (pinfunction "1_1") (pintype "unspecified"))
      (node (ref "U6") (pin "14") (pinfunction "IO20_14") (pintype "unspecified"))
    )
    (net (code "48") (name "Net-(U6-IO21)") (class "Default")
      (node (ref "H4") (pin "12") (pinfunction "12_12") (pintype "unspecified"))
      (node (ref "U6") (pin "23") (pinfunction "IO21_23") (pintype "unspecified"))
    )
    (net (code "49") (name "Net-(U6-IO39)") (class "Default")
      (node (ref "H4") (pin "8") (pinfunction "8_8") (pintype "unspecified"))
      (node (ref "U6") (pin "32") (pinfunction "IO39_32") (pintype "unspecified"))
    )
    (net (code "50") (name "Net-(U6-IO40)") (class "Default")
      (node (ref "H4") (pin "7") (pinfunction "7_7") (pintype "unspecified"))
      (node (ref "U6") (pin "33") (pinfunction "IO40_33") (pintype "unspecified"))
    )
    (net (code "51") (name "Net-(U6-IO41)") (class "Default")
      (node (ref "H4") (pin "6") (pinfunction "6_6") (pintype "unspecified"))
      (node (ref "U6") (pin "34") (pinfunction "IO41_34") (pintype "unspecified"))
    )
    (net (code "52") (name "Net-(U6-IO42)") (class "Default")
      (node (ref "H4") (pin "5") (pinfunction "5_5") (pintype "unspecified"))
      (node (ref "U6") (pin "35") (pinfunction "IO42_35") (pintype "unspecified"))
    )
    (net (code "53") (name "Net-(U6-IO45)") (class "Default")
      (node (ref "H4") (pin "9") (pinfunction "9_9") (pintype "unspecified"))
      (node (ref "U6") (pin "26") (pinfunction "IO45_26") (pintype "unspecified"))
    )
    (net (code "54") (name "Net-(U6-IO46)") (class "Default")
      (node (ref "H4") (pin "15") (pinfunction "15_15") (pintype "unspecified"))
      (node (ref "U6") (pin "16") (pinfunction "IO46_16") (pintype "unspecified"))
    )
    (net (code "55") (name "Net-(U6-IO47)") (class "Default")
      (node (ref "H4") (pin "11") (pinfunction "11_11") (pintype "unspecified"))
      (node (ref "U6") (pin "24") (pinfunction "IO47_24") (pintype "unspecified"))
    )
    (net (code "56") (name "Net-(U6-IO48)") (class "Default")
      (node (ref "H4") (pin "10") (pinfunction "10_10") (pintype "unspecified"))
      (node (ref "U6") (pin "25") (pinfunction "IO48_25") (pintype "unspecified"))
    )
    (net (code "57") (name "Net-(U6-RXD0)") (class "Default")
      (node (ref "H4") (pin "4") (pinfunction "4_4") (pintype "unspecified"))
      (node (ref "U6") (pin "36") (pinfunction "RXD0_36") (pintype "unspecified"))
    )
    (net (code "58") (name "Net-(U6-TXD0)") (class "Default")
      (node (ref "H4") (pin "3") (pinfunction "3_3") (pintype "unspecified"))
      (node (ref "U6") (pin "37") (pinfunction "TXD0_37") (pintype "unspecified"))
    )
    (net (code "59") (name "Net-(USB1-CC1)") (class "Default")
      (node (ref "R6") (pin "1") (pinfunction "1_1") (pintype "unspecified"))
      (node (ref "USB1") (pin "A5") (pinfunction "CC1_A5") (pintype "unspecified"))
    )
    (net (code "60") (name "Net-(USB1-CC2)") (class "Default")
      (node (ref "R7") (pin "1") (pinfunction "1_1") (pintype "unspecified"))
      (node (ref "USB1") (pin "B5") (pinfunction "CC2_B5") (pintype "unspecified"))
    )
    (net (code "61") (name "P0") (class "Default")
      (node (ref "R11") (pin "2") (pinfunction "2_2") (pintype "unspecified"))
      (node (ref "SW2") (pin "1") (pinfunction "A_1") (pintype "unspecified"))
      (node (ref "U6") (pin "27") (pinfunction "IO0_27") (pintype "unspecified"))
    )
    (net (code "62") (name "P16") (class "Default")
      (node (ref "R14") (pin "2") (pinfunction "2_2") (pintype "unspecified"))
      (node (ref "U6") (pin "9") (pinfunction "IO16_9") (pintype "unspecified"))
    )
    (net (code "63") (name "P17") (class "Default")
      (node (ref "U5") (pin "54") (pinfunction "UART1_TXD_54") (pintype "unspecified"))
      (node (ref "U6") (pin "10") (pinfunction "IO17_10") (pintype "unspecified"))
    )
    (net (code "64") (name "P18") (class "Default")
      (node (ref "U5") (pin "53") (pinfunction "UART1_RXD_53") (pintype "unspecified"))
      (node (ref "U6") (pin "11") (pinfunction "IO18_11") (pintype "unspecified"))
    )
    (net (code "65") (name "P35") (class "Default")
      (node (ref "U6") (pin "28") (pinfunction "IO35_28") (pintype "unspecified"))
      (node (ref "U9") (pin "3") (pinfunction "DE_3") (pintype "unspecified"))
    )
    (net (code "66") (name "P36") (class "Default")
      (node (ref "U6") (pin "29") (pinfunction "IO36_29") (pintype "unspecified"))
      (node (ref "U9") (pin "4") (pinfunction "DI_4") (pintype "unspecified"))
    )
    (net (code "67") (name "P37") (class "Default")
      (node (ref "U6") (pin "30") (pinfunction "IO37_30") (pintype "unspecified"))
      (node (ref "U9") (pin "1") (pinfunction "RO_1") (pintype "unspecified"))
    )
    (net (code "68") (name "P38") (class "Default")
      (node (ref "U6") (pin "31") (pinfunction "IO38_31") (pintype "unspecified"))
      (node (ref "U9") (pin "2") (pinfunction "RE#_2") (pintype "unspecified"))
    )
    (net (code "69") (name "SCK") (class "Default")
      (node (ref "H5") (pin "2") (pinfunction "2_2") (pintype "input"))
      (node (ref "R20") (pin "1") (pinfunction "1_1") (pintype "unspecified"))
      (node (ref "TF1") (pin "5") (pinfunction "CLK_5") (pintype "unspecified"))
      (node (ref "U6") (pin "20") (pinfunction "IO12_20") (pintype "unspecified"))
    )
    (net (code "70") (name "SPK_N") (class "Default")
      (node (ref "C19") (pin "2") (pinfunction "2_2") (pintype "unspecified"))
      (node (ref "R22") (pin "2") (pinfunction "2_2") (pintype "unspecified"))
      (node (ref "U5") (pin "14") (pinfunction "SPK_N_14") (pintype "unspecified"))
    )
    (net (code "71") (name "SPK_P") (class "Default")
      (node (ref "C18") (pin "2") (pinfunction "2_2") (pintype "unspecified"))
      (node (ref "R23") (pin "2") (pinfunction "2_2") (pintype "unspecified"))
      (node (ref "U5") (pin "13") (pinfunction "SPK_P_13") (pintype "unspecified"))
    )
    (net (code "72") (name "USB_DM") (class "Default")
      (node (ref "R12") (pin "2") (pinfunction "2_2") (pintype "unspecified"))
      (node (ref "USB1") (pin "A7") (pinfunction "D-_A7") (pintype "unspecified"))
      (node (ref "USB1") (pin "B7") (pinfunction "D-_B7") (pintype "unspecified"))
    )
    (net (code "73") (name "USB_DP") (class "Default")
      (node (ref "R13") (pin "2") (pinfunction "2_2") (pintype "unspecified"))
      (node (ref "USB1") (pin "A6") (pinfunction "D+_A6") (pintype "unspecified"))
      (node (ref "USB1") (pin "B6") (pinfunction "D+_B6") (pintype "unspecified"))
    )
    (net (code "74") (name "VBAT") (class "Default")
      (node (ref "C1") (pin "2") (pinfunction "2_2") (pintype "unspecified"))
      (node (ref "C12") (pin "1") (pinfunction "1_1") (pintype "input"))
      (node (ref "C13") (pin "1") (pinfunction "1_1") (pintype "input"))
      (node (ref "C14") (pin "1") (pinfunction "1_1") (pintype "unspecified"))
      (node (ref "C4") (pin "1") (pinfunction "1_1") (pintype "unspecified"))
      (node (ref "C6") (pin "2") (pinfunction "2_2") (pintype "input"))
      (node (ref "H1") (pin "1") (pinfunction "1_1") (pintype "unspecified"))
      (node (ref "H3") (pin "8") (pinfunction "8_8") (pintype "unspecified"))
      (node (ref "L2") (pin "1") (pinfunction "1_1") (pintype "unspecified"))
      (node (ref "R15") (pin "2") (pinfunction "2_2") (pintype "unspecified"))
      (node (ref "R16") (pin "2") (pinfunction "2_2") (pintype "unspecified"))
      (node (ref "R5") (pin "2") (pinfunction "2_2") (pintype "input"))
      (node (ref "U1") (pin "3") (pinfunction "VIN_3") (pintype "unspecified"))
      (node (ref "U3") (pin "5") (pinfunction "BAT_5") (pintype "unspecified"))
      (node (ref "U4") (pin "4") (pinfunction "EN_4") (pintype "unspecified"))
      (node (ref "U4") (pin "5") (pinfunction "IN_5") (pintype "unspecified"))
      (node (ref "U5") (pin "11") (pinfunction "VBAT_11") (pintype "unspecified"))
      (node (ref "U5") (pin "12") (pinfunction "VBAT_12") (pintype "unspecified"))
    )
    (net (code "75") (name "unconnected-(CARD1-Pad8)") (class "Default")
      (node (ref "CARD1") (pin "8") (pinfunction "8_8") (pintype "unspecified"))
    )
    (net (code "76") (name "unconnected-(CARD1-VPP-PadC6)") (class "Default")
      (node (ref "CARD1") (pin "C6") (pinfunction "VPP_C6") (pintype "unspecified"))
    )
    (net (code "77") (name "unconnected-(Q1-D12-Pad2)") (class "Default")
      (node (ref "Q1") (pin "2") (pinfunction "D12_2") (pintype "unspecified+no_connect"))
    )
    (net (code "78") (name "unconnected-(Q1-D12-Pad5)") (class "Default")
      (node (ref "Q1") (pin "5") (pinfunction "D12_5") (pintype "unspecified+no_connect"))
    )
    (net (code "79") (name "unconnected-(SW1-B-Pad2)") (class "Default")
      (node (ref "SW1") (pin "2") (pinfunction "B_2") (pintype "unspecified"))
    )
    (net (code "80") (name "unconnected-(SW1-C-Pad3)") (class "Default")
      (node (ref "SW1") (pin "3") (pinfunction "C_3") (pintype "unspecified"))
    )
    (net (code "81") (name "unconnected-(SW2-B-Pad2)") (class "Default")
      (node (ref "SW2") (pin "2") (pinfunction "B_2") (pintype "unspecified"))
    )
    (net (code "82") (name "unconnected-(SW2-C-Pad3)") (class "Default")
      (node (ref "SW2") (pin "3") (pinfunction "C_3") (pintype "unspecified"))
    )
    (net (code "83") (name "unconnected-(TF1-DAT1-Pad8)") (class "Default")
      (node (ref "TF1") (pin "8") (pinfunction "DAT1_8") (pintype "unspecified"))
    )
    (net (code "84") (name "unconnected-(TF1-DAT2-Pad1)") (class "Default")
      (node (ref "TF1") (pin "1") (pinfunction "DAT2_1") (pintype "unspecified"))
    )
    (net (code "85") (name "unconnected-(TF1-PadCD)") (class "Default")
      (node (ref "TF1") (pin "CD") (pinfunction "CD_CD") (pintype "unspecified"))
    )
    (net (code "86") (name "unconnected-(TF1-VSS-Pad6)") (class "Default")
      (node (ref "TF1") (pin "6") (pinfunction "VSS_6") (pintype "unspecified"))
    )
    (net (code "87") (name "unconnected-(U2-TD-Pad4)") (class "Default")
      (node (ref "U2") (pin "4") (pinfunction "TD_4") (pintype "unspecified+no_connect"))
    )
    (net (code "88") (name "unconnected-(U4-NC-Pad6)") (class "Default")
      (node (ref "U4") (pin "6") (pinfunction "NC_6") (pintype "unspecified+no_connect"))
    )
    (net (code "89") (name "unconnected-(U5-ADC0-Pad15)") (class "Default")
      (node (ref "U5") (pin "15") (pinfunction "ADC0_15") (pintype "unspecified"))
    )
    (net (code "90") (name "unconnected-(U5-ADC1-Pad16)") (class "Default")
      (node (ref "U5") (pin "16") (pinfunction "ADC1_16") (pintype "unspecified"))
    )
    (net (code "91") (name "unconnected-(U5-GND-Pad44)") (class "Default")
      (node (ref "U5") (pin "44") (pinfunction "GND_44") (pintype "unspecified"))
    )
    (net (code "92") (name "unconnected-(U5-GPS_CTS-Pad48)") (class "Default")
      (node (ref "U5") (pin "48") (pinfunction "GPS_CTS_48") (pintype "unspecified"))
    )
    (net (code "93") (name "unconnected-(U5-GPS_RTS-Pad47)") (class "Default")
      (node (ref "U5") (pin "47") (pinfunction "GPS_RTS_47") (pintype "unspecified"))
    )
    (net (code "94") (name "unconnected-(U5-GPS_RXD-Pad50)") (class "Default")
      (node (ref "U5") (pin "50") (pinfunction "GPS_RXD_50") (pintype "unspecified"))
    )
    (net (code "95") (name "unconnected-(U5-GPS_TXD-Pad49)") (class "Default")
      (node (ref "U5") (pin "49") (pinfunction "GPS_TXD_49") (pintype "unspecified"))
    )
    (net (code "96") (name "unconnected-(U5-HST_RXD-Pad38)") (class "Default")
      (node (ref "U5") (pin "38") (pinfunction "HST_RXD_38") (pintype "unspecified"))
    )
    (net (code "97") (name "unconnected-(U5-HST_TXD-Pad37)") (class "Default")
      (node (ref "U5") (pin "37") (pinfunction "HST_TXD_37") (pintype "unspecified"))
    )
    (net (code "98") (name "unconnected-(U5-I2C2_SCL-Pad1)") (class "Default")
      (node (ref "U5") (pin "1") (pinfunction "I2C2_SCL_1") (pintype "unspecified"))
    )
    (net (code "99") (name "unconnected-(U5-I2C2_SDA-Pad2)") (class "Default")
      (node (ref "U5") (pin "2") (pinfunction "I2C2_SDA_2") (pintype "unspecified"))
    )
    (net (code "100") (name "unconnected-(U5-IO25-Pad32)") (class "Default")
      (node (ref "U5") (pin "32") (pinfunction "IO25_32") (pintype "unspecified"))
    )
    (net (code "101") (name "unconnected-(U5-IO26-Pad25)") (class "Default")
      (node (ref "U5") (pin "25") (pinfunction "IO26_25") (pintype "unspecified"))
    )
    (net (code "102") (name "unconnected-(U5-IO27-Pad26)") (class "Default")
      (node (ref "U5") (pin "26") (pinfunction "IO27_26") (pintype "unspecified"))
    )
    (net (code "103") (name "unconnected-(U5-IO28-Pad30)") (class "Default")
      (node (ref "U5") (pin "30") (pinfunction "IO28_30") (pintype "unspecified"))
    )
    (net (code "104") (name "unconnected-(U5-IO29-Pad24)") (class "Default")
      (node (ref "U5") (pin "24") (pinfunction "IO29_24") (pintype "unspecified"))
    )
    (net (code "105") (name "unconnected-(U5-IO30-Pad31)") (class "Default")
      (node (ref "U5") (pin "31") (pinfunction "IO30_31") (pintype "unspecified"))
    )
    (net (code "106") (name "unconnected-(U5-LCD_CS-Pad19)") (class "Default")
      (node (ref "U5") (pin "19") (pinfunction "LCD_CS_19") (pintype "unspecified"))
    )
    (net (code "107") (name "unconnected-(U5-LCD_DIO-Pad21)") (class "Default")
      (node (ref "U5") (pin "21") (pinfunction "LCD_DIO_21") (pintype "unspecified"))
    )
    (net (code "108") (name "unconnected-(U5-LCD_RST-Pad20)") (class "Default")
      (node (ref "U5") (pin "20") (pinfunction "LCD_RST_20") (pintype "unspecified"))
    )
    (net (code "109") (name "unconnected-(U5-LCD_SCK-Pad23)") (class "Default")
      (node (ref "U5") (pin "23") (pinfunction "LCD_SCK_23") (pintype "unspecified"))
    )
    (net (code "110") (name "unconnected-(U5-LCD_SDO-Pad22)") (class "Default")
      (node (ref "U5") (pin "22") (pinfunction "LCD_SDO_22") (pintype "unspecified"))
    )
    (net (code "111") (name "unconnected-(U5-SD_CLK-Pad8)") (class "Default")
      (node (ref "U5") (pin "8") (pinfunction "SD_CLK_8") (pintype "unspecified"))
    )
    (net (code "112") (name "unconnected-(U5-SD_CMD-Pad7)") (class "Default")
      (node (ref "U5") (pin "7") (pinfunction "SD_CMD_7") (pintype "unspecified"))
    )
    (net (code "113") (name "unconnected-(U5-SD_D0-Pad6)") (class "Default")
      (node (ref "U5") (pin "6") (pinfunction "SD_D0_6") (pintype "unspecified"))
    )
    (net (code "114") (name "unconnected-(U5-SD_D1-Pad5)") (class "Default")
      (node (ref "U5") (pin "5") (pinfunction "SD_D1_5") (pintype "unspecified"))
    )
    (net (code "115") (name "unconnected-(U5-SD_D2-Pad4)") (class "Default")
      (node (ref "U5") (pin "4") (pinfunction "SD_D2_4") (pintype "unspecified"))
    )
    (net (code "116") (name "unconnected-(U5-SD_D3-Pad3)") (class "Default")
      (node (ref "U5") (pin "3") (pinfunction "SD_D3_3") (pintype "unspecified"))
    )
    (net (code "117") (name "unconnected-(U5-UART1_CTS-Pad52)") (class "Default")
      (node (ref "U5") (pin "52") (pinfunction "UART1_CTS_52") (pintype "unspecified"))
    )
    (net (code "118") (name "unconnected-(U5-UART1_RTS-Pad51)") (class "Default")
      (node (ref "U5") (pin "51") (pinfunction "UART1_RTS_51") (pintype "unspecified"))
    )
    (net (code "119") (name "unconnected-(U5-USB_N-Pad35)") (class "Default")
      (node (ref "U5") (pin "35") (pinfunction "USB_N_35") (pintype "unspecified"))
    )
    (net (code "120") (name "unconnected-(U5-USB_P-Pad36)") (class "Default")
      (node (ref "U5") (pin "36") (pinfunction "USB_P_36") (pintype "unspecified"))
    )
    (net (code "121") (name "unconnected-(U5-VBUS-Pad17)") (class "Default")
      (node (ref "U5") (pin "17") (pinfunction "VBUS_17") (pintype "unspecified"))
    )
    (net (code "122") (name "unconnected-(U5-VIO-Pad43)") (class "Default")
      (node (ref "U5") (pin "43") (pinfunction "VIO_43") (pintype "unspecified"))
    )
    (net (code "123") (name "unconnected-(USB1-SBU1-PadA8)") (class "Default")
      (node (ref "USB1") (pin "A8") (pinfunction "SBU1_A8") (pintype "unspecified"))
    )
    (net (code "124") (name "unconnected-(USB1-SBU2-PadB8)") (class "Default")
      (node (ref "USB1") (pin "B8") (pinfunction "SBU2_B8") (pintype "unspecified"))
    )
  )
)
